# TMP117.net
KiCad netlist of a schematic drawn in Altium Designer
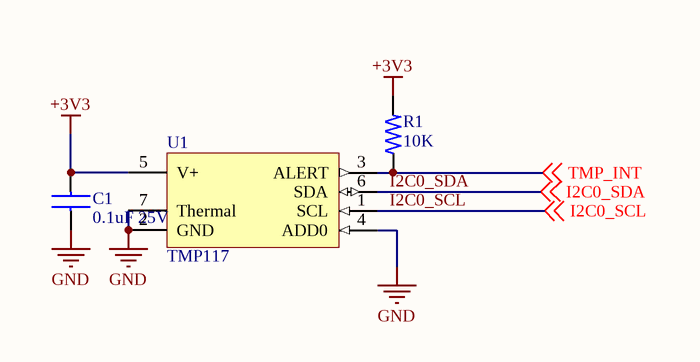
[diagram p0: TMP117.SchDoc]

(export (version "E")
  (design (tool "Eeschema 10.0.6"))
  (components
    (comp (ref "C1")
      (value "0.1uF 25V")
      (footprint "Chip2Pin_1.6x0.8x0.9_CAP")
      (description "Cap Ceramic 0.1uF 25V X7R 10% Pad SMD 0603 Soft Termination 125C Automotive T/R")
      (fields
        (field (name "MANUFACTURER") "Murata")
        (field (name "MANUFACTURER PART NUMBER") "GCJ188R71E104KA12D")
      )
      (libsource (lib "LPEDT_Parts") (part "GCJ188R71E104KA12D"))
    )
    (comp (ref "R1")
      (value "10K")
      (footprint "RES_0603_1608X06")
      (description "Res Thin Film 0603 10K Ohm 0.5% 1/10W ±25ppm/°C Molded SMD Paper T/R")
      (fields
        (field (name "MANUFACTURER") "Yageo")
        (field (name "MANUFACTURER PART NUMBER") "RT0603DRD0710KL")
      )
      (libsource (lib "LPEDT_Parts") (part "RT0603DRD0710KL"))
    )
    (comp (ref "U1")
      (value "TMP117")
      (footprint "6-DFN-2x2")
      (description "0.1C digital temperature sensor, 48-bit EEPROM, PT100/PT1000 RTD replacement 6-WSON 0 to 85")
      (fields
        (field (name "MANUFACTURER") "Texas Instruments")
        (field (name "MANUFACTURER PART NUMBER") "TMP117MAIDRVT")
      )
      (libsource (lib "LPEDT_Parts") (part "TMP117MAIDRVT"))
    )
  )
  (nets
    (net (code "1") (name "+3V3") (class "Default")
      (node (ref "C1") (pin "1") (pinfunction "1_1") (pintype "passive"))
      (node (ref "R1") (pin "2") (pinfunction "2_2") (pintype "passive"))
      (node (ref "U1") (pin "5") (pinfunction "V+_5") (pintype "power_in"))
    )
    (net (code "2") (name "GND") (class "Default")
      (node (ref "C1") (pin "2") (pinfunction "2_2") (pintype "passive"))
      (node (ref "U1") (pin "2") (pinfunction "GND_2") (pintype "passive"))
      (node (ref "U1") (pin "4") (pinfunction "ADD0_4") (pintype "input"))
      (node (ref "U1") (pin "7") (pinfunction "Thermal_7") (pintype "passive"))
    )
    (net (code "3") (name "I2C0_SCL") (class "Default")
      (node (ref "U1") (pin "1") (pinfunction "SCL_1") (pintype "input"))
    )
    (net (code "4") (name "I2C0_SDA") (class "Default")
      (node (ref "U1") (pin "6") (pinfunction "SDA_6") (pintype "bidirectional"))
    )
    (net (code "5") (name "TMP_INT") (class "Default")
      (node (ref "R1") (pin "1") (pinfunction "1_1") (pintype "passive"))
      (node (ref "U1") (pin "3") (pinfunction "ALERT_3") (pintype "output"))
    )
  )
)
